# 2211B_SysArrosage_auto.net
KiCad netlist of a schematic drawn in Altium Designer
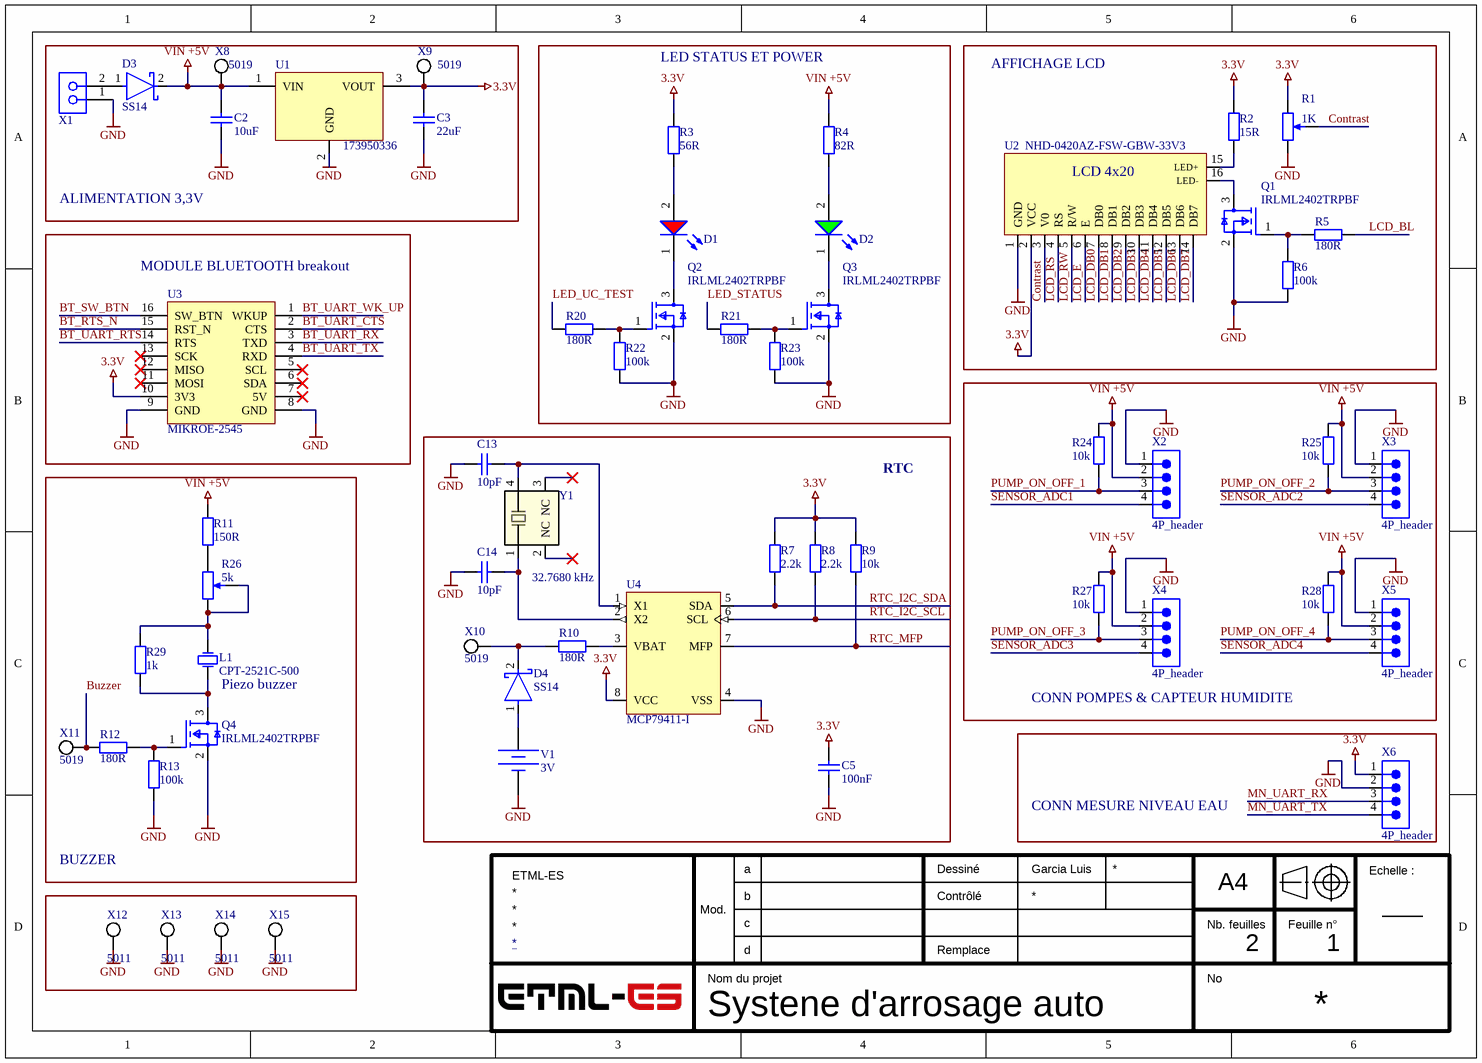
[diagram p0: 2211B_SysArrosage_auto.SchDoc]

(export (version "E")
  (design (tool "Eeschema 10.0.6"))
  (components
    (comp (ref "C2")
      (value "10uF")
      (footprint "CAPC2013X145X48NL20T23")
      (libsource (lib "Sys_Arossage") (part "Capacitor_Non-Polarized"))
    )
    (comp (ref "C3")
      (value "22uF")
      (footprint "CAPC2013X145X48NL20T23")
      (libsource (lib "Sys_Arossage") (part "Capacitor_Non-Polarized"))
    )
    (comp (ref "C5")
      (value "100nF")
      (footprint "CAPC2013X145X48NL20T23")
      (libsource (lib "Sys_Arossage") (part "Capacitor_Non-Polarized"))
    )
    (comp (ref "C13")
      (value "10pF")
      (footprint "CAPC2013X145X48NL20T23")
      (libsource (lib "Sys_Arossage") (part "Capacitor_Non-Polarized"))
    )
    (comp (ref "C14")
      (value "10pF")
      (footprint "CAPC2013X145X48NL20T23")
      (libsource (lib "Sys_Arossage") (part "Capacitor_Non-Polarized"))
    )
    (comp (ref "D1")
      (value "LED_Red_2A-1K")
      (footprint "LEDC2012X75N")
      (description "LED Uni-Color Hyper Red 640nm 2-Pin Chip LED T/R")
      (fields
        (field (name "MANUFACTURER") "Kingbright")
        (field (name "MANUFACTURER PART NUMBER") "APT2012SECK/J3-PRV")
      )
      (libsource (lib "Sys_Arossage") (part "LED_Red_2A-1K"))
    )
    (comp (ref "D2")
      (value "LED_Green_2A-1K")
      (footprint "LEDC2012X75N")
      (description "LED Uni-Color Green 515nm 2-Pin SMD T/R")
      (fields
        (field (name "MANUFACTURER") "Kingbright")
        (field (name "MANUFACTURER PART NUMBER") "APHCM2012ZGCK-F01")
      )
      (libsource (lib "Sys_Arossage") (part "LED_Green_2A-1K"))
    )
    (comp (ref "D3")
      (value "SS14")
      (footprint "FP-403AE-MFG")
      (description "DIODE SCHOTTKY 40V 1A SMA")
      (fields
        (field (name "MANUFACTURER") "ON Semiconductor")
        (field (name "OCTOPART") "https://octopart.com/ss14-on+semiconductor-29205033")
      )
      (libsource (lib "Sys_Arossage") (part "CMP-2000-04943-2"))
    )
    (comp (ref "D4")
      (value "SS14")
      (footprint "FP-403AE-MFG")
      (description "DIODE SCHOTTKY 40V 1A SMA")
      (fields
        (field (name "MANUFACTURER") "ON Semiconductor")
        (field (name "OCTOPART") "https://octopart.com/ss14-on+semiconductor-29205033")
      )
      (libsource (lib "Sys_Arossage") (part "CMP-2000-04943-2"))
    )
    (comp (ref "L1")
      (value "CPT-2521C-500")
      (footprint "61300211121")
      (description "AUDIO PIEZO TRANSDUCER 50V CHAS")
      (fields (field (name "MANUFACTURER") "CUI Devices"))
      (libsource (lib "Sys_Arossage") (part "Buzzer"))
    )
    (comp (ref "Q1")
      (value "IRLML2402TRPBF")
      (footprint "FP-Micro3-IPC_C")
      (description "MOSFET N-CH 20V 1.2A SOT-23")
      (fields (field (name "MANUFACTURER") "Infineon"))
      (libsource (lib "Sys_Arossage") (part "CMP-32901-000179-1"))
    )
    (comp (ref "Q2")
      (value "IRLML2402TRPBF")
      (footprint "FP-Micro3-IPC_C")
      (description "MOSFET N-CH 20V 1.2A SOT-23")
      (fields (field (name "MANUFACTURER") "Infineon"))
      (libsource (lib "Sys_Arossage") (part "CMP-32901-000179-1"))
    )
    (comp (ref "Q3")
      (value "IRLML2402TRPBF")
      (footprint "FP-Micro3-IPC_C")
      (description "MOSFET N-CH 20V 1.2A SOT-23")
      (fields (field (name "MANUFACTURER") "Infineon"))
      (libsource (lib "Sys_Arossage") (part "CMP-32901-000179-1"))
    )
    (comp (ref "Q4")
      (value "IRLML2402TRPBF")
      (footprint "FP-Micro3-IPC_C")
      (description "MOSFET N-CH 20V 1.2A SOT-23")
      (fields (field (name "MANUFACTURER") "Infineon"))
      (libsource (lib "Sys_Arossage") (part "CMP-32901-000179-1"))
    )
    (comp (ref "R1")
      (value "1K")
      (footprint "TRIM_3362P-1-1K")
      (description "In a Tube of 50, 1kO Through Hole Trimmer Potentiometer 0.5W Top Adjust Bourns 3362 Series")
      (fields
        (field (name "MANUFACTURER") "Bourns")
        (field (name "MANUFACTURER PART NUMBER") "3362P-1-102LF")
        (field (name "PUBLISHER") "Altium Limited")
      )
      (libsource (lib "Sys_Arossage") (part "RPot"))
    )
    (comp (ref "R2")
      (value "15R")
      (footprint "RESC2012X60N")
      (description "SMD Chip Resistor, 10 kOhm, ± 1%, 125 mW, 0805 [2012 Metric], Thick Film, General Purpose")
      (fields
        (field (name "MANUFACTURER") "Yageo")
        (field (name "MANUFACTURER PART NUMBER") "RC0805FR-0710KL")
      )
      (libsource (lib "Sys_Arossage") (part "R-SMD"))
    )
    (comp (ref "R3")
      (value "56R")
      (footprint "RESC2012X60N")
      (description "SMD Chip Resistor, 10 kOhm, ± 1%, 125 mW, 0805 [2012 Metric], Thick Film, General Purpose")
      (fields
        (field (name "MANUFACTURER") "Yageo")
        (field (name "MANUFACTURER PART NUMBER") "RC0805FR-0710KL")
      )
      (libsource (lib "Sys_Arossage") (part "R-SMD"))
    )
    (comp (ref "R4")
      (value "82R")
      (footprint "RESC2012X60N")
      (description "SMD Chip Resistor, 10 kOhm, ± 1%, 125 mW, 0805 [2012 Metric], Thick Film, General Purpose")
      (fields
        (field (name "MANUFACTURER") "Yageo")
        (field (name "MANUFACTURER PART NUMBER") "RC0805FR-0710KL")
      )
      (libsource (lib "Sys_Arossage") (part "R-SMD"))
    )
    (comp (ref "R5")
      (value "180R")
      (footprint "RESC2012X60N")
      (description "SMD Chip Resistor, 10 kOhm, ± 1%, 125 mW, 0805 [2012 Metric], Thick Film, General Purpose")
      (fields
        (field (name "MANUFACTURER") "Yageo")
        (field (name "MANUFACTURER PART NUMBER") "RC0805FR-0710KL")
      )
      (libsource (lib "") (part "R-SMD_1"))
    )
    (comp (ref "R6")
      (value "100k")
      (footprint "RESC2012X60N")
      (description "SMD Chip Resistor, 10 kOhm, ± 1%, 125 mW, 0805 [2012 Metric], Thick Film, General Purpose")
      (fields
        (field (name "MANUFACTURER") "Yageo")
        (field (name "MANUFACTURER PART NUMBER") "RC0805FR-0710KL")
      )
      (libsource (lib "Sys_Arossage") (part "R-SMD"))
    )
    (comp (ref "R7")
      (value "2.2k")
      (footprint "RESC2012X60N")
      (description "SMD Chip Resistor, 10 kOhm, ± 1%, 125 mW, 0805 [2012 Metric], Thick Film, General Purpose")
      (fields
        (field (name "MANUFACTURER") "Yageo")
        (field (name "MANUFACTURER PART NUMBER") "RC0805FR-0710KL")
      )
      (libsource (lib "Sys_Arossage") (part "R-SMD"))
    )
    (comp (ref "R8")
      (value "2.2k")
      (footprint "RESC2012X60N")
      (description "SMD Chip Resistor, 10 kOhm, ± 1%, 125 mW, 0805 [2012 Metric], Thick Film, General Purpose")
      (fields
        (field (name "MANUFACTURER") "Yageo")
        (field (name "MANUFACTURER PART NUMBER") "RC0805FR-0710KL")
      )
      (libsource (lib "Sys_Arossage") (part "R-SMD"))
    )
    (comp (ref "R9")
      (value "10k")
      (footprint "RESC2012X60N")
      (description "SMD Chip Resistor, 10 kOhm, ± 1%, 125 mW, 0805 [2012 Metric], Thick Film, General Purpose")
      (fields
        (field (name "MANUFACTURER") "Yageo")
        (field (name "MANUFACTURER PART NUMBER") "RC0805FR-0710KL")
      )
      (libsource (lib "Sys_Arossage") (part "R-SMD"))
    )
    (comp (ref "R10")
      (value "180R")
      (footprint "RESC2012X60N")
      (description "SMD Chip Resistor, 10 kOhm, ± 1%, 125 mW, 0805 [2012 Metric], Thick Film, General Purpose")
      (fields
        (field (name "MANUFACTURER") "Yageo")
        (field (name "MANUFACTURER PART NUMBER") "RC0805FR-0710KL")
      )
      (libsource (lib "") (part "R-SMD_1"))
    )
    (comp (ref "R11")
      (value "150R")
      (footprint "RESC2012X60N")
      (description "SMD Chip Resistor, 10 kOhm, ± 1%, 125 mW, 0805 [2012 Metric], Thick Film, General Purpose")
      (fields
        (field (name "MANUFACTURER") "Yageo")
        (field (name "MANUFACTURER PART NUMBER") "RC0805FR-0710KL")
      )
      (libsource (lib "Sys_Arossage") (part "R-SMD"))
    )
    (comp (ref "R12")
      (value "180R")
      (footprint "RESC2012X60N")
      (description "SMD Chip Resistor, 10 kOhm, ± 1%, 125 mW, 0805 [2012 Metric], Thick Film, General Purpose")
      (fields
        (field (name "MANUFACTURER") "Yageo")
        (field (name "MANUFACTURER PART NUMBER") "RC0805FR-0710KL")
      )
      (libsource (lib "") (part "R-SMD_1"))
    )
    (comp (ref "R13")
      (value "100k")
      (footprint "RESC2012X60N")
      (description "SMD Chip Resistor, 10 kOhm, ± 1%, 125 mW, 0805 [2012 Metric], Thick Film, General Purpose")
      (fields
        (field (name "MANUFACTURER") "Yageo")
        (field (name "MANUFACTURER PART NUMBER") "RC0805FR-0710KL")
      )
      (libsource (lib "") (part "R-SMD_2"))
    )
    (comp (ref "R20")
      (value "180R")
      (footprint "RESC2012X60N")
      (description "SMD Chip Resistor, 10 kOhm, ± 1%, 125 mW, 0805 [2012 Metric], Thick Film, General Purpose")
      (fields
        (field (name "MANUFACTURER") "Yageo")
        (field (name "MANUFACTURER PART NUMBER") "RC0805FR-0710KL")
      )
      (libsource (lib "") (part "R-SMD_1"))
    )
    (comp (ref "R21")
      (value "180R")
      (footprint "RESC2012X60N")
      (description "SMD Chip Resistor, 10 kOhm, ± 1%, 125 mW, 0805 [2012 Metric], Thick Film, General Purpose")
      (fields
        (field (name "MANUFACTURER") "Yageo")
        (field (name "MANUFACTURER PART NUMBER") "RC0805FR-0710KL")
      )
      (libsource (lib "") (part "R-SMD_1"))
    )
    (comp (ref "R22")
      (value "100k")
      (footprint "RESC2012X60N")
      (description "SMD Chip Resistor, 10 kOhm, ± 1%, 125 mW, 0805 [2012 Metric], Thick Film, General Purpose")
      (fields
        (field (name "MANUFACTURER") "Yageo")
        (field (name "MANUFACTURER PART NUMBER") "RC0805FR-0710KL")
      )
      (libsource (lib "Sys_Arossage") (part "R-SMD"))
    )
    (comp (ref "R23")
      (value "100k")
      (footprint "RESC2012X60N")
      (description "SMD Chip Resistor, 10 kOhm, ± 1%, 125 mW, 0805 [2012 Metric], Thick Film, General Purpose")
      (fields
        (field (name "MANUFACTURER") "Yageo")
        (field (name "MANUFACTURER PART NUMBER") "RC0805FR-0710KL")
      )
      (libsource (lib "Sys_Arossage") (part "R-SMD"))
    )
    (comp (ref "R24")
      (value "10k")
      (footprint "RESC2012X60N")
      (description "SMD Chip Resistor, 10 kOhm, ± 1%, 125 mW, 0805 [2012 Metric], Thick Film, General Purpose")
      (fields
        (field (name "MANUFACTURER") "Yageo")
        (field (name "MANUFACTURER PART NUMBER") "RC0805FR-0710KL")
      )
      (libsource (lib "Sys_Arossage") (part "R-SMD"))
    )
    (comp (ref "R25")
      (value "10k")
      (footprint "RESC2012X60N")
      (description "SMD Chip Resistor, 10 kOhm, ± 1%, 125 mW, 0805 [2012 Metric], Thick Film, General Purpose")
      (fields
        (field (name "MANUFACTURER") "Yageo")
        (field (name "MANUFACTURER PART NUMBER") "RC0805FR-0710KL")
      )
      (libsource (lib "Sys_Arossage") (part "R-SMD"))
    )
    (comp (ref "R26")
      (value "5k")
      (footprint "TRIM_3386P-1-502LF_5K")
      (description "Cermet Not Linear VERTICAL Trimmer Potentiometer 卤10% 280deg 500mW 85C")
      (fields
        (field (name "MANUFACTURER") "Bourns")
        (field (name "MANUFACTURER PART NUMBER") "3386P-1-502LF")
      )
      (libsource (lib "Sys_Arossage") (part "Rpot_5K"))
    )
    (comp (ref "R27")
      (value "10k")
      (footprint "RESC2012X60N")
      (description "SMD Chip Resistor, 10 kOhm, ± 1%, 125 mW, 0805 [2012 Metric], Thick Film, General Purpose")
      (fields
        (field (name "MANUFACTURER") "Yageo")
        (field (name "MANUFACTURER PART NUMBER") "RC0805FR-0710KL")
      )
      (libsource (lib "Sys_Arossage") (part "R-SMD"))
    )
    (comp (ref "R28")
      (value "10k")
      (footprint "RESC2012X60N")
      (description "SMD Chip Resistor, 10 kOhm, ± 1%, 125 mW, 0805 [2012 Metric], Thick Film, General Purpose")
      (fields
        (field (name "MANUFACTURER") "Yageo")
        (field (name "MANUFACTURER PART NUMBER") "RC0805FR-0710KL")
      )
      (libsource (lib "Sys_Arossage") (part "R-SMD"))
    )
    (comp (ref "R29")
      (value "1k")
      (footprint "RESC2012X60N")
      (description "SMD Chip Resistor, 10 kOhm, ± 1%, 125 mW, 0805 [2012 Metric], Thick Film, General Purpose")
      (fields
        (field (name "MANUFACTURER") "Yageo")
        (field (name "MANUFACTURER PART NUMBER") "RC0805FR-0710KL")
      )
      (libsource (lib "Sys_Arossage") (part "R-SMD"))
    )
    (comp (ref "U1")
      (value "173950336")
      (footprint "WPME-FDSM_SIP-3_L11.6W7.55H10.16")
      (description "173950336 WPME-FDSM Fixed Step Down Regulator Module")
      (libsource (lib "Altium Content Vault") (part "SIP-3_WPME-FDSM"))
    )
    (comp (ref "U2")
      (value "NHD-0420AZ-FSW-GBW-33V3")
      (footprint "NHD-0420AZ-FSW-GBW-33V3")
      (description "Character Display STN Transflective 20Char x 4Line 16-Pin")
      (fields (field (name "MANUFACTURER") "Newhaven Display"))
      (libsource (lib "Sys_Arossage") (part "NHD-0420AZ-FSW-GBW-33V3"))
    )
    (comp (ref "U3")
      (value "MIKROE-2545")
      (footprint "RN4678 CLICK V3")
      (description "RN4678 Click Bluetooth Communications Module")
      (fields (field (name "MANUFACTURER") "mikroElektronika"))
      (libsource (lib "Sys_Arossage") (part "RN4678_CLICK_SOCKET"))
    )
    (comp (ref "U4")
      (value "MCP79411-I")
      (footprint "SOIC-SN8_M")
      (description "Real Time Clock Serial 64byte Clock/Calendar/Alarm/Battery Backup Automotive 8-Pin SOIC N Tube")
      (fields
        (field (name "MANUFACTURER") "Microchip")
        (field (name "MANUFACTURER PART NUMBER") "MCP79411-I/SN")
      )
      (libsource (lib "Sys_Arossage") (part "RTC"))
    )
    (comp (ref "V1")
      (value "Pile 3V")
      (footprint "BAT_BU2032SM-HD-G")
      (description "pile 3V")
      (fields (field (name "DC MAGNITUDE") "3V"))
      (libsource (lib "Sys_Arossage") (part "Battery"))
    )
    (comp (ref "X1")
      (value "Header 1x2")
      (footprint "691214110002")
      (description "Conn Terminal Block 2 POS 3.5mm Solder ST Thru-Hole 10A Box")
      (fields
        (field (name "MANUFACTURER") "Wurth Electronics")
        (field (name "MANUFACTURER PART NUMBER") "691214110002")
      )
      (libsource (lib "Sys_Arossage") (part "Header 1x2"))
    )
    (comp (ref "X2")
      (value "4P_header")
      (footprint "61300411121")
      (description "THT Vertical Pin Header WR-PHD, Pitch 2.54 mm, Single Row, 4 pins")
      (fields
        (field (name "MANUFACTURER") "Wurth Electronics")
        (field (name "MANUFACTURER PART NUMBER") "61300411121")
      )
      (libsource (lib "Sys_Arossage") (part "4P_header"))
    )
    (comp (ref "X3")
      (value "4P_header")
      (footprint "61300411121")
      (description "THT Vertical Pin Header WR-PHD, Pitch 2.54 mm, Single Row, 4 pins")
      (fields
        (field (name "MANUFACTURER") "Wurth Electronics")
        (field (name "MANUFACTURER PART NUMBER") "61300411121")
      )
      (libsource (lib "Sys_Arossage") (part "4P_header"))
    )
    (comp (ref "X4")
      (value "4P_header")
      (footprint "61300411121")
      (description "THT Vertical Pin Header WR-PHD, Pitch 2.54 mm, Single Row, 4 pins")
      (fields
        (field (name "MANUFACTURER") "Wurth Electronics")
        (field (name "MANUFACTURER PART NUMBER") "61300411121")
      )
      (libsource (lib "Sys_Arossage") (part "4P_header"))
    )
    (comp (ref "X5")
      (value "4P_header")
      (footprint "61300411121")
      (description "THT Vertical Pin Header WR-PHD, Pitch 2.54 mm, Single Row, 4 pins")
      (fields
        (field (name "MANUFACTURER") "Wurth Electronics")
        (field (name "MANUFACTURER PART NUMBER") "61300411121")
      )
      (libsource (lib "Sys_Arossage") (part "4P_header"))
    )
    (comp (ref "X6")
      (value "4P_header")
      (footprint "61300411121")
      (description "THT Vertical Pin Header WR-PHD, Pitch 2.54 mm, Single Row, 4 pins")
      (fields
        (field (name "MANUFACTURER") "Wurth Electronics")
        (field (name "MANUFACTURER PART NUMBER") "61300411121")
      )
      (libsource (lib "Sys_Arossage") (part "4P_header"))
    )
    (comp (ref "X8")
      (value "5019")
      (footprint "KEYSTONE_5019")
      (description "Test Point, Mini, SMT, Phos Bronze/Silver, 1000pc Tape & Reel ¦ Keystone Electronics 5019")
      (fields (field (name "MANUFACTURER") "Keystone") (field (name "MANUFACTURER_1") "Keystone Electronics"))
      (libsource (lib "Sys_Arossage") (part "TEST_POINT_SMD"))
    )
    (comp (ref "X9")
      (value "5019")
      (footprint "KEYSTONE_5019")
      (description "Test Point, Mini, SMT, Phos Bronze/Silver, 1000pc Tape & Reel ¦ Keystone Electronics 5019")
      (fields (field (name "MANUFACTURER") "Keystone") (field (name "MANUFACTURER_1") "Keystone Electronics"))
      (libsource (lib "Sys_Arossage") (part "TEST_POINT_SMD"))
    )
    (comp (ref "X10")
      (value "5019")
      (footprint "KEYSTONE_5019")
      (description "Test Point, Mini, SMT, Phos Bronze/Silver, 1000pc Tape & Reel ¦ Keystone Electronics 5019")
      (fields (field (name "MANUFACTURER") "Keystone") (field (name "MANUFACTURER_1") "Keystone Electronics"))
      (libsource (lib "Sys_Arossage") (part "TEST_POINT_SMD"))
    )
    (comp (ref "X11")
      (value "5019")
      (footprint "KEYSTONE_5019")
      (description "Test Point, Mini, SMT, Phos Bronze/Silver, 1000pc Tape & Reel ¦ Keystone Electronics 5019")
      (fields (field (name "MANUFACTURER") "Keystone") (field (name "MANUFACTURER_1") "Keystone Electronics"))
      (libsource (lib "Sys_Arossage") (part "TEST_POINT_SMD"))
    )
    (comp (ref "X12")
      (value "5011")
      (footprint "Keystone_5011")
      (fields (field (name "MANUFACTURER") "Keystone") (field (name "MANUFACTURER_1") "Keystone Electronics"))
      (libsource (lib "Sys_Arossage") (part "TEST_POINT_THT"))
    )
    (comp (ref "X13")
      (value "5011")
      (footprint "Keystone_5011")
      (fields (field (name "MANUFACTURER") "Keystone") (field (name "MANUFACTURER_1") "Keystone Electronics"))
      (libsource (lib "Sys_Arossage") (part "TEST_POINT_THT"))
    )
    (comp (ref "X14")
      (value "5011")
      (footprint "Keystone_5011")
      (fields (field (name "MANUFACTURER") "Keystone") (field (name "MANUFACTURER_1") "Keystone Electronics"))
      (libsource (lib "Sys_Arossage") (part "TEST_POINT_THT"))
    )
    (comp (ref "X15")
      (value "5011")
      (footprint "Keystone_5011")
      (fields (field (name "MANUFACTURER") "Keystone") (field (name "MANUFACTURER_1") "Keystone Electronics"))
      (libsource (lib "Sys_Arossage") (part "TEST_POINT_THT"))
    )
    (comp (ref "Y1")
      (value "32.7680 kHz")
      (footprint "SOJ_MC-306_EPS-M")
      (description "CRYSTAL 32.7680KHZ 12.5PF SMD")
      (fields
        (field (name "MANUFACTURER_PART_NUMBER") "MC-306 32.7680K-A3: ROHS")
        (field (name "MANUFACTURER") "Epson")
        (field (name "COPYRIGHT") "Copyright (C) 2024 Ultra Librarian. All rights reserved.")
      )
      (libsource (lib "Sys_Arossage") (part "MC-306 32.7680K-A3{colon} ROHS"))
    )
  )
  (nets
    (net (code "1") (name "/BT_RTS_N") (class "Default")
      (node (ref "U3") (pin "15") (pinfunction "RST_N_15") (pintype "passive"))
    )
    (net (code "2") (name "/BT_SW_BTN") (class "Default")
      (node (ref "U3") (pin "16") (pinfunction "SW_BTN_16") (pintype "passive"))
    )
    (net (code "3") (name "/BT_UART_CTS") (class "Default")
      (node (ref "U3") (pin "2") (pinfunction "CTS_2") (pintype "passive"))
    )
    (net (code "4") (name "/BT_UART_RTS") (class "Default")
      (node (ref "U3") (pin "14") (pinfunction "RTS_14") (pintype "passive"))
    )
    (net (code "5") (name "/BT_UART_RX") (class "Default")
      (node (ref "U3") (pin "3") (pinfunction "TXD_3") (pintype "passive"))
    )
    (net (code "6") (name "/BT_UART_TX") (class "Default")
      (node (ref "U3") (pin "4") (pinfunction "RXD_4") (pintype "passive"))
    )
    (net (code "7") (name "/BT_UART_WK_UP") (class "Default")
      (node (ref "U3") (pin "1") (pinfunction "WKUP_1") (pintype "passive"))
    )
    (net (code "8") (name "/Buzzer") (class "Default")
      (node (ref "R12") (pin "2") (pinfunction "2_2") (pintype "passive"))
      (node (ref "X11") (pin "1") (pinfunction "TP_1") (pintype "passive"))
    )
    (net (code "9") (name "/Contrast") (class "Default")
      (node (ref "R1") (pin "2") (pinfunction "W_2") (pintype "passive"))
      (node (ref "U2") (pin "3") (pinfunction "V0_3") (pintype "passive"))
    )
    (net (code "10") (name "/LCD_BL") (class "Default")
      (node (ref "R5") (pin "1") (pinfunction "1_1") (pintype "passive"))
    )
    (net (code "11") (name "/LCD_DB0") (class "Default")
      (node (ref "U2") (pin "7") (pinfunction "DB0_7") (pintype "passive"))
    )
    (net (code "12") (name "/LCD_DB1") (class "Default")
      (node (ref "U2") (pin "8") (pinfunction "DB1_8") (pintype "passive"))
    )
    (net (code "13") (name "/LCD_DB2") (class "Default")
      (node (ref "U2") (pin "9") (pinfunction "DB2_9") (pintype "passive"))
    )
    (net (code "14") (name "/LCD_DB3") (class "Default")
      (node (ref "U2") (pin "10") (pinfunction "DB3_10") (pintype "passive"))
    )
    (net (code "15") (name "/LCD_DB4") (class "Default")
      (node (ref "U2") (pin "11") (pinfunction "DB4_11") (pintype "passive"))
    )
    (net (code "16") (name "/LCD_DB5") (class "Default")
      (node (ref "U2") (pin "12") (pinfunction "DB5_12") (pintype "passive"))
    )
    (net (code "17") (name "/LCD_DB6") (class "Default")
      (node (ref "U2") (pin "13") (pinfunction "DB6_13") (pintype "passive"))
    )
    (net (code "18") (name "/LCD_DB7") (class "Default")
      (node (ref "U2") (pin "14") (pinfunction "DB7_14") (pintype "passive"))
    )
    (net (code "19") (name "/LCD_E") (class "Default")
      (node (ref "U2") (pin "6") (pinfunction "E_6") (pintype "passive"))
    )
    (net (code "20") (name "/LCD_RS") (class "Default")
      (node (ref "U2") (pin "4") (pinfunction "RS_4") (pintype "passive"))
    )
    (net (code "21") (name "/LCD_RW") (class "Default")
      (node (ref "U2") (pin "5") (pinfunction "R/W_5") (pintype "passive"))
    )
    (net (code "22") (name "/LED_STATUS") (class "Default")
      (node (ref "R21") (pin "2") (pinfunction "2_2") (pintype "passive"))
    )
    (net (code "23") (name "/LED_UC_TEST") (class "Default")
      (node (ref "R20") (pin "2") (pinfunction "2_2") (pintype "passive"))
    )
    (net (code "24") (name "/MN_UART_RX") (class "Default")
      (node (ref "X6") (pin "3") (pinfunction "3_3") (pintype "passive"))
    )
    (net (code "25") (name "/MN_UART_TX") (class "Default")
      (node (ref "X6") (pin "4") (pinfunction "4_4") (pintype "passive"))
    )
    (net (code "26") (name "/PUMP_ON_OFF_1") (class "Default")
      (node (ref "R24") (pin "1") (pinfunction "1_1") (pintype "passive"))
      (node (ref "X2") (pin "3") (pinfunction "3_3") (pintype "passive"))
    )
    (net (code "27") (name "/PUMP_ON_OFF_2") (class "Default")
      (node (ref "R25") (pin "1") (pinfunction "1_1") (pintype "passive"))
      (node (ref "X3") (pin "3") (pinfunction "3_3") (pintype "passive"))
    )
    (net (code "28") (name "/PUMP_ON_OFF_3") (class "Default")
      (node (ref "R27") (pin "1") (pinfunction "1_1") (pintype "passive"))
      (node (ref "X4") (pin "3") (pinfunction "3_3") (pintype "passive"))
    )
    (net (code "29") (name "/PUMP_ON_OFF_4") (class "Default")
      (node (ref "R28") (pin "1") (pinfunction "1_1") (pintype "passive"))
      (node (ref "X5") (pin "3") (pinfunction "3_3") (pintype "passive"))
    )
    (net (code "30") (name "/RTC_I2C_SCL") (class "Default")
      (node (ref "R8") (pin "1") (pinfunction "1_1") (pintype "passive"))
      (node (ref "U4") (pin "6") (pinfunction "SCL_6") (pintype "input"))
    )
    (net (code "31") (name "/RTC_I2C_SDA") (class "Default")
      (node (ref "R7") (pin "1") (pinfunction "1_1") (pintype "passive"))
      (node (ref "U4") (pin "5") (pinfunction "SDA_5") (pintype "bidirectional"))
    )
    (net (code "32") (name "/RTC_MFP") (class "Default")
      (node (ref "R9") (pin "1") (pinfunction "1_1") (pintype "passive"))
      (node (ref "U4") (pin "7") (pinfunction "MFP_7") (pintype "open_collector"))
    )
    (net (code "33") (name "/SENSOR_ADC1") (class "Default")
      (node (ref "X2") (pin "4") (pinfunction "4_4") (pintype "passive"))
    )
    (net (code "34") (name "/SENSOR_ADC2") (class "Default")
      (node (ref "X3") (pin "4") (pinfunction "4_4") (pintype "passive"))
    )
    (net (code "35") (name "/SENSOR_ADC3") (class "Default")
      (node (ref "X4") (pin "4") (pinfunction "4_4") (pintype "passive"))
    )
    (net (code "36") (name "/SENSOR_ADC4") (class "Default")
      (node (ref "X5") (pin "4") (pinfunction "4_4") (pintype "passive"))
    )
    (net (code "37") (name "3.3V") (class "Default")
      (node (ref "C3") (pin "2") (pinfunction "2_2") (pintype "passive"))
      (node (ref "C5") (pin "2") (pinfunction "2_2") (pintype "passive"))
      (node (ref "R1") (pin "3") (pinfunction "CW_3") (pintype "passive"))
      (node (ref "R2") (pin "2") (pinfunction "2_2") (pintype "passive"))
      (node (ref "R3") (pin "2") (pinfunction "2_2") (pintype "passive"))
      (node (ref "R7") (pin "2") (pinfunction "2_2") (pintype "passive"))
      (node (ref "R8") (pin "2") (pinfunction "2_2") (pintype "passive"))
      (node (ref "R9") (pin "2") (pinfunction "2_2") (pintype "passive"))
      (node (ref "U1") (pin "3") (pinfunction "VOUT_3") (pintype "passive"))
      (node (ref "U2") (pin "2") (pinfunction "VCC_2") (pintype "passive"))
      (node (ref "U3") (pin "10") (pinfunction "3V3_10") (pintype "passive"))
      (node (ref "U4") (pin "8") (pinfunction "VCC_8") (pintype "passive"))
      (node (ref "X6") (pin "1") (pinfunction "1_1") (pintype "passive"))
      (node (ref "X9") (pin "1") (pinfunction "TP_1") (pintype "passive"))
    )
    (net (code "38") (name "GND") (class "Default")
      (node (ref "C13") (pin "1") (pinfunction "1_1") (pintype "passive"))
      (node (ref "C14") (pin "1") (pinfunction "1_1") (pintype "passive"))
      (node (ref "C2") (pin "1") (pinfunction "1_1") (pintype "passive"))
      (node (ref "C3") (pin "1") (pinfunction "1_1") (pintype "passive"))
      (node (ref "C5") (pin "1") (pinfunction "1_1") (pintype "passive"))
      (node (ref "Q1") (pin "2") (pinfunction "S_2") (pintype "passive"))
      (node (ref "Q2") (pin "2") (pinfunction "S_2") (pintype "passive"))
      (node (ref "Q3") (pin "2") (pinfunction "S_2") (pintype "passive"))
      (node (ref "Q4") (pin "2") (pinfunction "S_2") (pintype "passive"))
      (node (ref "R1") (pin "1") (pinfunction "CCW_1") (pintype "passive"))
      (node (ref "R13") (pin "2") (pinfunction "2_2") (pintype "passive"))
      (node (ref "R22") (pin "1") (pinfunction "1_1") (pintype "passive"))
      (node (ref "R23") (pin "1") (pinfunction "1_1") (pintype "passive"))
      (node (ref "R6") (pin "1") (pinfunction "1_1") (pintype "passive"))
      (node (ref "U1") (pin "2") (pinfunction "GND_2") (pintype "passive"))
      (node (ref "U2") (pin "1") (pinfunction "GND_1") (pintype "passive"))
      (node (ref "U3") (pin "8") (pinfunction "GND_8") (pintype "passive"))
      (node (ref "U3") (pin "9") (pinfunction "GND_9") (pintype "passive"))
      (node (ref "U4") (pin "4") (pinfunction "VSS_4") (pintype "passive"))
      (node (ref "V1") (pin "2") (pinfunction "2_2") (pintype "passive"))
      (node (ref "X1") (pin "1") (pinfunction "1_1") (pintype "passive"))
      (node (ref "X12") (pin "1") (pinfunction "TP_1") (pintype "passive"))
      (node (ref "X13") (pin "1") (pinfunction "TP_1") (pintype "passive"))
      (node (ref "X14") (pin "1") (pinfunction "TP_1") (pintype "passive"))
      (node (ref "X15") (pin "1") (pinfunction "TP_1") (pintype "passive"))
      (node (ref "X2") (pin "1") (pinfunction "1_1") (pintype "passive"))
      (node (ref "X3") (pin "1") (pinfunction "1_1") (pintype "passive"))
      (node (ref "X4") (pin "1") (pinfunction "1_1") (pintype "passive"))
      (node (ref "X5") (pin "1") (pinfunction "1_1") (pintype "passive"))
      (node (ref "X6") (pin "2") (pinfunction "2_2") (pintype "passive"))
    )
    (net (code "39") (name "Net-(D1-A)") (class "Default")
      (node (ref "D1") (pin "2") (pinfunction "A_2") (pintype "passive"))
      (node (ref "R3") (pin "1") (pinfunction "1_1") (pintype "passive"))
    )
    (net (code "40") (name "Net-(D1-K)") (class "Default")
      (node (ref "D1") (pin "1") (pinfunction "K_1") (pintype "passive"))
      (node (ref "Q2") (pin "3") (pinfunction "D_3") (pintype "passive"))
    )
    (net (code "41") (name "Net-(D2-A)") (class "Default")
      (node (ref "D2") (pin "2") (pinfunction "A_2") (pintype "passive"))
      (node (ref "R4") (pin "1") (pinfunction "1_1") (pintype "passive"))
    )
    (net (code "42") (name "Net-(D2-K)") (class "Default")
      (node (ref "D2") (pin "1") (pinfunction "K_1") (pintype "passive"))
      (node (ref "Q3") (pin "3") (pinfunction "D_3") (pintype "passive"))
    )
    (net (code "43") (name "Net-(D3-A)") (class "Default")
      (node (ref "D3") (pin "1") (pinfunction "A_1") (pintype "passive"))
      (node (ref "X1") (pin "2") (pinfunction "2_2") (pintype "passive"))
    )
    (net (code "44") (name "Net-(D4-A)") (class "Default")
      (node (ref "D4") (pin "1") (pinfunction "A_1") (pintype "passive"))
      (node (ref "V1") (pin "1") (pinfunction "1_1") (pintype "passive"))
    )
    (net (code "45") (name "Net-(D4-C)") (class "Default")
      (node (ref "D4") (pin "2") (pinfunction "C_2") (pintype "passive"))
      (node (ref "R10") (pin "2") (pinfunction "2_2") (pintype "passive"))
      (node (ref "X10") (pin "1") (pinfunction "TP_1") (pintype "passive"))
    )
    (net (code "46") (name "Net-(Q1-D)") (class "Default")
      (node (ref "Q1") (pin "3") (pinfunction "D_3") (pintype "passive"))
      (node (ref "U2") (pin "16") (pinfunction "LED-_16") (pintype "passive"))
    )
    (net (code "47") (name "Net-(Q1-G)") (class "Default")
      (node (ref "Q1") (pin "1") (pinfunction "G_1") (pintype "passive"))
      (node (ref "R5") (pin "2") (pinfunction "2_2") (pintype "passive"))
      (node (ref "R6") (pin "2") (pinfunction "2_2") (pintype "passive"))
    )
    (net (code "48") (name "Net-(Q2-G)") (class "Default")
      (node (ref "Q2") (pin "1") (pinfunction "G_1") (pintype "passive"))
      (node (ref "R20") (pin "1") (pinfunction "1_1") (pintype "passive"))
      (node (ref "R22") (pin "2") (pinfunction "2_2") (pintype "passive"))
    )
    (net (code "49") (name "Net-(Q3-G)") (class "Default")
      (node (ref "Q3") (pin "1") (pinfunction "G_1") (pintype "passive"))
      (node (ref "R21") (pin "1") (pinfunction "1_1") (pintype "passive"))
      (node (ref "R23") (pin "2") (pinfunction "2_2") (pintype "passive"))
    )
    (net (code "50") (name "Net-(Q4-D)") (class "Default")
      (node (ref "L1") (pin "1") (pintype "passive"))
      (node (ref "Q4") (pin "3") (pinfunction "D_3") (pintype "passive"))
      (node (ref "R29") (pin "1") (pinfunction "1_1") (pintype "passive"))
    )
    (net (code "51") (name "Net-(Q4-G)") (class "Default")
      (node (ref "Q4") (pin "1") (pinfunction "G_1") (pintype "passive"))
      (node (ref "R12") (pin "1") (pinfunction "1_1") (pintype "passive"))
      (node (ref "R13") (pin "1") (pinfunction "1_1") (pintype "passive"))
    )
    (net (code "52") (name "Net-(R26-CCW)") (class "Default")
      (node (ref "L1") (pin "2") (pintype "passive"))
      (node (ref "R26") (pin "1") (pinfunction "CCW_1") (pintype "passive"))
      (node (ref "R26") (pin "2") (pinfunction "W_2") (pintype "passive"))
      (node (ref "R29") (pin "2") (pinfunction "2_2") (pintype "passive"))
    )
    (net (code "53") (name "Net-(R26-CW)") (class "Default")
      (node (ref "R11") (pin "1") (pinfunction "1_1") (pintype "passive"))
      (node (ref "R26") (pin "3") (pinfunction "CW_3") (pintype "passive"))
    )
    (net (code "54") (name "Net-(U2-LED+)") (class "Default")
      (node (ref "R2") (pin "1") (pinfunction "1_1") (pintype "passive"))
      (node (ref "U2") (pin "15") (pinfunction "LED+_15") (pintype "passive"))
    )
    (net (code "55") (name "Net-(U4-VBAT)") (class "Default")
      (node (ref "R10") (pin "1") (pinfunction "1_1") (pintype "passive"))
      (node (ref "U4") (pin "3") (pinfunction "VBAT_3") (pintype "power_in"))
    )
    (net (code "56") (name "Net-(U4-X1)") (class "Default")
      (node (ref "C13") (pin "2") (pinfunction "2_2") (pintype "passive"))
      (node (ref "U4") (pin "1") (pinfunction "X1_1") (pintype "input"))
      (node (ref "Y1") (pin "4") (pinfunction "4_4") (pintype "passive"))
    )
    (net (code "57") (name "Net-(U4-X2)") (class "Default")
      (node (ref "C14") (pin "2") (pinfunction "2_2") (pintype "passive"))
      (node (ref "U4") (pin "2") (pinfunction "X2_2") (pintype "output"))
      (node (ref "Y1") (pin "1") (pinfunction "1_1") (pintype "passive"))
    )
    (net (code "58") (name "VIN +5V") (class "Default")
      (node (ref "C2") (pin "2") (pinfunction "2_2") (pintype "passive"))
      (node (ref "D3") (pin "2") (pinfunction "C_2") (pintype "passive"))
      (node (ref "R11") (pin "2") (pinfunction "2_2") (pintype "passive"))
      (node (ref "R24") (pin "2") (pinfunction "2_2") (pintype "passive"))
      (node (ref "R25") (pin "2") (pinfunction "2_2") (pintype "passive"))
      (node (ref "R27") (pin "2") (pinfunction "2_2") (pintype "passive"))
      (node (ref "R28") (pin "2") (pinfunction "2_2") (pintype "passive"))
      (node (ref "R4") (pin "2") (pinfunction "2_2") (pintype "passive"))
      (node (ref "U1") (pin "1") (pinfunction "VIN_1") (pintype "passive"))
      (node (ref "X2") (pin "2") (pinfunction "2_2") (pintype "passive"))
      (node (ref "X3") (pin "2") (pinfunction "2_2") (pintype "passive"))
      (node (ref "X4") (pin "2") (pinfunction "2_2") (pintype "passive"))
      (node (ref "X5") (pin "2") (pinfunction "2_2") (pintype "passive"))
      (node (ref "X8") (pin "1") (pinfunction "TP_1") (pintype "passive"))
    )
    (net (code "59") (name "unconnected-(U3-5V-Pad7)") (class "Default")
      (node (ref "U3") (pin "7") (pinfunction "5V_7") (pintype "passive+no_connect"))
    )
    (net (code "60") (name "unconnected-(U3-MISO-Pad12)") (class "Default")
      (node (ref "U3") (pin "12") (pinfunction "MISO_12") (pintype "passive+no_connect"))
    )
    (net (code "61") (name "unconnected-(U3-MOSI-Pad11)") (class "Default")
      (node (ref "U3") (pin "11") (pinfunction "MOSI_11") (pintype "passive+no_connect"))
    )
    (net (code "62") (name "unconnected-(U3-SCK-Pad13)") (class "Default")
      (node (ref "U3") (pin "13") (pinfunction "SCK_13") (pintype "passive+no_connect"))
    )
    (net (code "63") (name "unconnected-(U3-SCL-Pad5)") (class "Default")
      (node (ref "U3") (pin "5") (pinfunction "SCL_5") (pintype "passive+no_connect"))
    )
    (net (code "64") (name "unconnected-(U3-SDA-Pad6)") (class "Default")
      (node (ref "U3") (pin "6") (pinfunction "SDA_6") (pintype "passive+no_connect"))
    )
    (net (code "65") (name "unconnected-(Y1-NC-Pad2)") (class "Default")
      (node (ref "Y1") (pin "2") (pinfunction "NC_2") (pintype "passive+no_connect"))
    )
    (net (code "66") (name "unconnected-(Y1-NC-Pad3)") (class "Default")
      (node (ref "Y1") (pin "3") (pinfunction "NC_3") (pintype "passive+no_connect"))
    )
  )
)
